# con-right-top.net
KiCad netlist of a schematic drawn in Altium Designer
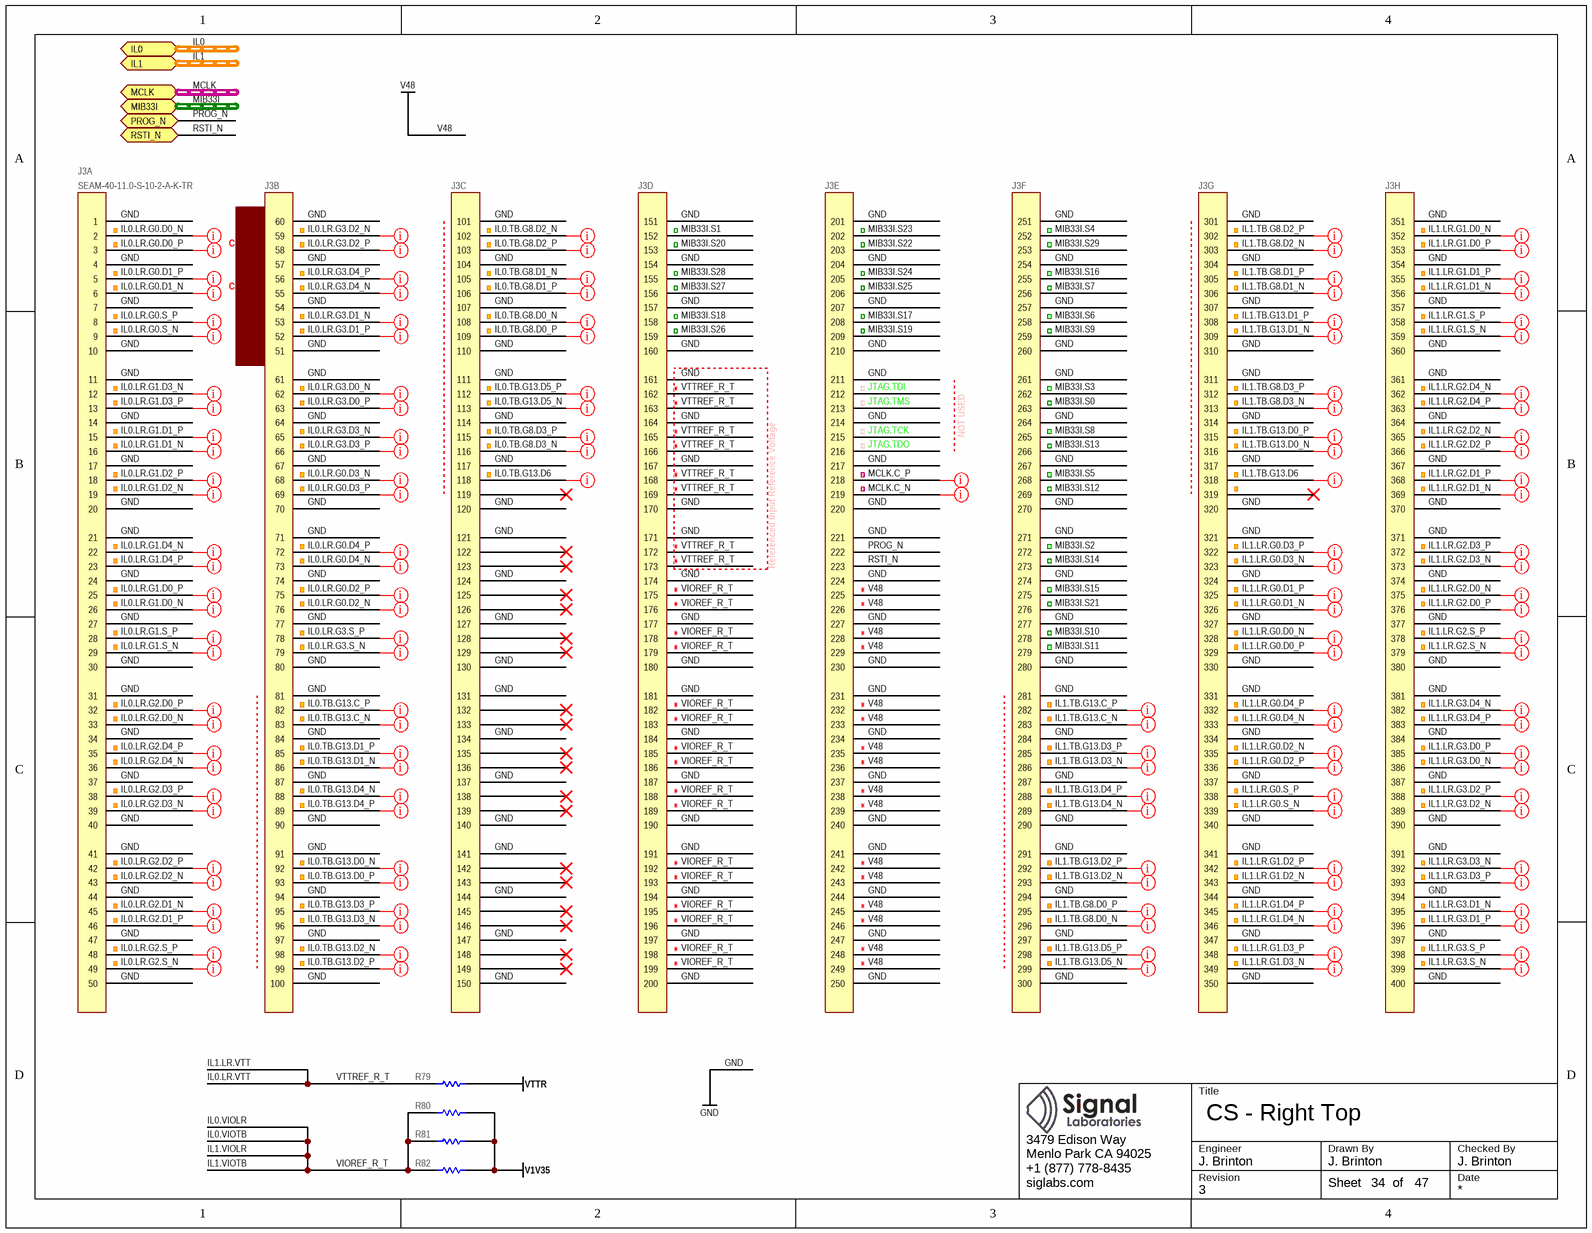
[diagram p0: con-right-top.SchDoc]

(export (version "E")
  (design (tool "Eeschema 10.0.6"))
  (components
    (comp (ref "J3")
      (value "SEAM-40-11.0-S-10-2-A-K-TR")
      (footprint "samtec:SEAM-40-11.0-S-10-2-A-K-TR")
      (description "Terminal Array Assembly, Surface Mount, 0.050\" Pitch, 400 Pins")
      (fields (field (name "MANUFACTURER") "Samtec"))
      (libsource (lib "samtec") (part "SEAM-40-11.0-S-10-2-A-K-TR"))
    )
    (comp (ref "R79")
      (value "SOLDER_LINK")
      (footprint "SOLDERLINK0603X26N")
      (description "Solder Link")
      (libsource (lib "generic") (part "RES"))
    )
    (comp (ref "R80")
      (value "SOLDER_LINK")
      (footprint "SOLDERLINK0603X26N")
      (description "Solder Link")
      (libsource (lib "generic") (part "RES"))
    )
    (comp (ref "R81")
      (value "SOLDER_LINK")
      (footprint "SOLDERLINK0603X26N")
      (description "Solder Link")
      (libsource (lib "generic") (part "RES"))
    )
    (comp (ref "R82")
      (value "SOLDER_LINK")
      (footprint "SOLDERLINK0603X26N")
      (description "Solder Link")
      (libsource (lib "generic") (part "RES"))
    )
  )
  (nets
    (net (code "5") (name "/IL0.LR.G0.D0_N") (class "Default")
      (node (ref "J3") (pin "2") (pinfunction "2_2") (pintype "passive"))
    )
    (net (code "6") (name "/IL0.LR.G0.D0_P") (class "Default")
      (node (ref "J3") (pin "3") (pinfunction "3_3") (pintype "passive"))
    )
    (net (code "7") (name "/IL0.LR.G0.D1_N") (class "Default")
      (node (ref "J3") (pin "6") (pinfunction "6_6") (pintype "passive"))
    )
    (net (code "8") (name "/IL0.LR.G0.D1_P") (class "Default")
      (node (ref "J3") (pin "5") (pinfunction "5_5") (pintype "passive"))
    )
    (net (code "9") (name "/IL0.LR.G0.D2_N") (class "Default")
      (node (ref "J3") (pin "76") (pinfunction "76_76") (pintype "passive"))
    )
    (net (code "10") (name "/IL0.LR.G0.D2_P") (class "Default")
      (node (ref "J3") (pin "75") (pinfunction "75_75") (pintype "passive"))
    )
    (net (code "11") (name "/IL0.LR.G0.D3_N") (class "Default")
      (node (ref "J3") (pin "68") (pinfunction "68_68") (pintype "passive"))
    )
    (net (code "12") (name "/IL0.LR.G0.D3_P") (class "Default")
      (node (ref "J3") (pin "69") (pinfunction "69_69") (pintype "passive"))
    )
    (net (code "13") (name "/IL0.LR.G0.D4_N") (class "Default")
      (node (ref "J3") (pin "73") (pinfunction "73_73") (pintype "passive"))
    )
    (net (code "14") (name "/IL0.LR.G0.D4_P") (class "Default")
      (node (ref "J3") (pin "72") (pinfunction "72_72") (pintype "passive"))
    )
    (net (code "15") (name "/IL0.LR.G0.S_N") (class "Default")
      (node (ref "J3") (pin "9") (pinfunction "9_9") (pintype "passive"))
    )
    (net (code "16") (name "/IL0.LR.G0.S_P") (class "Default")
      (node (ref "J3") (pin "8") (pinfunction "8_8") (pintype "passive"))
    )
    (net (code "17") (name "/IL0.LR.G1.D0_N") (class "Default")
      (node (ref "J3") (pin "26") (pinfunction "26_26") (pintype "passive"))
    )
    (net (code "18") (name "/IL0.LR.G1.D0_P") (class "Default")
      (node (ref "J3") (pin "25") (pinfunction "25_25") (pintype "passive"))
    )
    (net (code "19") (name "/IL0.LR.G1.D1_N") (class "Default")
      (node (ref "J3") (pin "16") (pinfunction "16_16") (pintype "passive"))
    )
    (net (code "20") (name "/IL0.LR.G1.D1_P") (class "Default")
      (node (ref "J3") (pin "15") (pinfunction "15_15") (pintype "passive"))
    )
    (net (code "21") (name "/IL0.LR.G1.D2_N") (class "Default")
      (node (ref "J3") (pin "19") (pinfunction "19_19") (pintype "passive"))
    )
    (net (code "22") (name "/IL0.LR.G1.D2_P") (class "Default")
      (node (ref "J3") (pin "18") (pinfunction "18_18") (pintype "passive"))
    )
    (net (code "23") (name "/IL0.LR.G1.D3_N") (class "Default")
      (node (ref "J3") (pin "12") (pinfunction "12_12") (pintype "passive"))
    )
    (net (code "24") (name "/IL0.LR.G1.D3_P") (class "Default")
      (node (ref "J3") (pin "13") (pinfunction "13_13") (pintype "passive"))
    )
    (net (code "25") (name "/IL0.LR.G1.D4_N") (class "Default")
      (node (ref "J3") (pin "22") (pinfunction "22_22") (pintype "passive"))
    )
    (net (code "26") (name "/IL0.LR.G1.D4_P") (class "Default")
      (node (ref "J3") (pin "23") (pinfunction "23_23") (pintype "passive"))
    )
    (net (code "27") (name "/IL0.LR.G1.S_N") (class "Default")
      (node (ref "J3") (pin "29") (pinfunction "29_29") (pintype "passive"))
    )
    (net (code "28") (name "/IL0.LR.G1.S_P") (class "Default")
      (node (ref "J3") (pin "28") (pinfunction "28_28") (pintype "passive"))
    )
    (net (code "29") (name "/IL0.LR.G2.D0_N") (class "Default")
      (node (ref "J3") (pin "33") (pinfunction "33_33") (pintype "passive"))
    )
    (net (code "30") (name "/IL0.LR.G2.D0_P") (class "Default")
      (node (ref "J3") (pin "32") (pinfunction "32_32") (pintype "passive"))
    )
    (net (code "31") (name "/IL0.LR.G2.D1_N") (class "Default")
      (node (ref "J3") (pin "45") (pinfunction "45_45") (pintype "passive"))
    )
    (net (code "32") (name "/IL0.LR.G2.D1_P") (class "Default")
      (node (ref "J3") (pin "46") (pinfunction "46_46") (pintype "passive"))
    )
    (net (code "33") (name "/IL0.LR.G2.D2_N") (class "Default")
      (node (ref "J3") (pin "43") (pinfunction "43_43") (pintype "passive"))
    )
    (net (code "34") (name "/IL0.LR.G2.D2_P") (class "Default")
      (node (ref "J3") (pin "42") (pinfunction "42_42") (pintype "passive"))
    )
    (net (code "35") (name "/IL0.LR.G2.D3_N") (class "Default")
      (node (ref "J3") (pin "39") (pinfunction "39_39") (pintype "passive"))
    )
    (net (code "36") (name "/IL0.LR.G2.D3_P") (class "Default")
      (node (ref "J3") (pin "38") (pinfunction "38_38") (pintype "passive"))
    )
    (net (code "37") (name "/IL0.LR.G2.D4_N") (class "Default")
      (node (ref "J3") (pin "36") (pinfunction "36_36") (pintype "passive"))
    )
    (net (code "38") (name "/IL0.LR.G2.D4_P") (class "Default")
      (node (ref "J3") (pin "35") (pinfunction "35_35") (pintype "passive"))
    )
    (net (code "39") (name "/IL0.LR.G2.S_N") (class "Default")
      (node (ref "J3") (pin "49") (pinfunction "49_49") (pintype "passive"))
    )
    (net (code "40") (name "/IL0.LR.G2.S_P") (class "Default")
      (node (ref "J3") (pin "48") (pinfunction "48_48") (pintype "passive"))
    )
    (net (code "41") (name "/IL0.LR.G3.D0_N") (class "Default")
      (node (ref "J3") (pin "62") (pinfunction "62_62") (pintype "passive"))
    )
    (net (code "42") (name "/IL0.LR.G3.D0_P") (class "Default")
      (node (ref "J3") (pin "63") (pinfunction "63_63") (pintype "passive"))
    )
    (net (code "43") (name "/IL0.LR.G3.D1_N") (class "Default")
      (node (ref "J3") (pin "53") (pinfunction "53_53") (pintype "passive"))
    )
    (net (code "44") (name "/IL0.LR.G3.D1_P") (class "Default")
      (node (ref "J3") (pin "52") (pinfunction "52_52") (pintype "passive"))
    )
    (net (code "45") (name "/IL0.LR.G3.D2_N") (class "Default")
      (node (ref "J3") (pin "59") (pinfunction "59_59") (pintype "passive"))
    )
    (net (code "46") (name "/IL0.LR.G3.D2_P") (class "Default")
      (node (ref "J3") (pin "58") (pinfunction "58_58") (pintype "passive"))
    )
    (net (code "47") (name "/IL0.LR.G3.D3_N") (class "Default")
      (node (ref "J3") (pin "65") (pinfunction "65_65") (pintype "passive"))
    )
    (net (code "48") (name "/IL0.LR.G3.D3_P") (class "Default")
      (node (ref "J3") (pin "66") (pinfunction "66_66") (pintype "passive"))
    )
    (net (code "49") (name "/IL0.LR.G3.D4_N") (class "Default")
      (node (ref "J3") (pin "55") (pinfunction "55_55") (pintype "passive"))
    )
    (net (code "50") (name "/IL0.LR.G3.D4_P") (class "Default")
      (node (ref "J3") (pin "56") (pinfunction "56_56") (pintype "passive"))
    )
    (net (code "51") (name "/IL0.LR.G3.S_N") (class "Default")
      (node (ref "J3") (pin "79") (pinfunction "79_79") (pintype "passive"))
    )
    (net (code "52") (name "/IL0.LR.G3.S_P") (class "Default")
      (node (ref "J3") (pin "78") (pinfunction "78_78") (pintype "passive"))
    )
    (net (code "53") (name "/IL0.LR.VTT") (class "Default")
      (node (ref "J3") (pin "162") (pinfunction "162_162") (pintype "passive"))
      (node (ref "J3") (pin "163") (pinfunction "163_163") (pintype "passive"))
      (node (ref "J3") (pin "165") (pinfunction "165_165") (pintype "passive"))
      (node (ref "J3") (pin "166") (pinfunction "166_166") (pintype "passive"))
      (node (ref "J3") (pin "168") (pinfunction "168_168") (pintype "passive"))
      (node (ref "J3") (pin "169") (pinfunction "169_169") (pintype "passive"))
      (node (ref "J3") (pin "172") (pinfunction "172_172") (pintype "passive"))
      (node (ref "J3") (pin "173") (pinfunction "173_173") (pintype "passive"))
      (node (ref "R79") (pin "2") (pinfunction "2_2") (pintype "passive"))
    )
    (net (code "54") (name "/IL0.TB.G8.D0_N") (class "Default")
      (node (ref "J3") (pin "108") (pinfunction "108_108") (pintype "passive"))
    )
    (net (code "55") (name "/IL0.TB.G8.D0_P") (class "Default")
      (node (ref "J3") (pin "109") (pinfunction "109_109") (pintype "passive"))
    )
    (net (code "56") (name "/IL0.TB.G8.D1_N") (class "Default")
      (node (ref "J3") (pin "105") (pinfunction "105_105") (pintype "passive"))
    )
    (net (code "57") (name "/IL0.TB.G8.D1_P") (class "Default")
      (node (ref "J3") (pin "106") (pinfunction "106_106") (pintype "passive"))
    )
    (net (code "58") (name "/IL0.TB.G8.D2_N") (class "Default")
      (node (ref "J3") (pin "102") (pinfunction "102_102") (pintype "passive"))
    )
    (net (code "59") (name "/IL0.TB.G8.D2_P") (class "Default")
      (node (ref "J3") (pin "103") (pinfunction "103_103") (pintype "passive"))
    )
    (net (code "60") (name "/IL0.TB.G8.D3_N") (class "Default")
      (node (ref "J3") (pin "116") (pinfunction "116_116") (pintype "passive"))
    )
    (net (code "61") (name "/IL0.TB.G8.D3_P") (class "Default")
      (node (ref "J3") (pin "115") (pinfunction "115_115") (pintype "passive"))
    )
    (net (code "62") (name "/IL0.TB.G13.C_N") (class "Default")
      (node (ref "J3") (pin "83") (pinfunction "83_83") (pintype "passive"))
    )
    (net (code "63") (name "/IL0.TB.G13.C_P") (class "Default")
      (node (ref "J3") (pin "82") (pinfunction "82_82") (pintype "passive"))
    )
    (net (code "64") (name "/IL0.TB.G13.D0_N") (class "Default")
      (node (ref "J3") (pin "92") (pinfunction "92_92") (pintype "passive"))
    )
    (net (code "65") (name "/IL0.TB.G13.D0_P") (class "Default")
      (node (ref "J3") (pin "93") (pinfunction "93_93") (pintype "passive"))
    )
    (net (code "66") (name "/IL0.TB.G13.D1_N") (class "Default")
      (node (ref "J3") (pin "86") (pinfunction "86_86") (pintype "passive"))
    )
    (net (code "67") (name "/IL0.TB.G13.D1_P") (class "Default")
      (node (ref "J3") (pin "85") (pinfunction "85_85") (pintype "passive"))
    )
    (net (code "68") (name "/IL0.TB.G13.D2_N") (class "Default")
      (node (ref "J3") (pin "98") (pinfunction "98_98") (pintype "passive"))
    )
    (net (code "69") (name "/IL0.TB.G13.D2_P") (class "Default")
      (node (ref "J3") (pin "99") (pinfunction "99_99") (pintype "passive"))
    )
    (net (code "70") (name "/IL0.TB.G13.D3_N") (class "Default")
      (node (ref "J3") (pin "96") (pinfunction "96_96") (pintype "passive"))
    )
    (net (code "71") (name "/IL0.TB.G13.D3_P") (class "Default")
      (node (ref "J3") (pin "95") (pinfunction "95_95") (pintype "passive"))
    )
    (net (code "72") (name "/IL0.TB.G13.D4_N") (class "Default")
      (node (ref "J3") (pin "88") (pinfunction "88_88") (pintype "passive"))
    )
    (net (code "73") (name "/IL0.TB.G13.D4_P") (class "Default")
      (node (ref "J3") (pin "89") (pinfunction "89_89") (pintype "passive"))
    )
    (net (code "74") (name "/IL0.TB.G13.D5_N") (class "Default")
      (node (ref "J3") (pin "113") (pinfunction "113_113") (pintype "passive"))
    )
    (net (code "75") (name "/IL0.TB.G13.D5_P") (class "Default")
      (node (ref "J3") (pin "112") (pinfunction "112_112") (pintype "passive"))
    )
    (net (code "76") (name "/IL0.TB.G13.D6") (class "Default")
      (node (ref "J3") (pin "118") (pinfunction "118_118") (pintype "passive"))
    )
    (net (code "77") (name "/IL0.VIOLR") (class "Default")
      (node (ref "J3") (pin "175") (pinfunction "175_175") (pintype "passive"))
      (node (ref "J3") (pin "176") (pinfunction "176_176") (pintype "passive"))
      (node (ref "J3") (pin "178") (pinfunction "178_178") (pintype "passive"))
      (node (ref "J3") (pin "179") (pinfunction "179_179") (pintype "passive"))
      (node (ref "J3") (pin "182") (pinfunction "182_182") (pintype "passive"))
      (node (ref "J3") (pin "183") (pinfunction "183_183") (pintype "passive"))
      (node (ref "J3") (pin "185") (pinfunction "185_185") (pintype "passive"))
      (node (ref "J3") (pin "186") (pinfunction "186_186") (pintype "passive"))
      (node (ref "J3") (pin "188") (pinfunction "188_188") (pintype "passive"))
      (node (ref "J3") (pin "189") (pinfunction "189_189") (pintype "passive"))
      (node (ref "J3") (pin "192") (pinfunction "192_192") (pintype "passive"))
      (node (ref "J3") (pin "193") (pinfunction "193_193") (pintype "passive"))
      (node (ref "J3") (pin "195") (pinfunction "195_195") (pintype "passive"))
      (node (ref "J3") (pin "196") (pinfunction "196_196") (pintype "passive"))
      (node (ref "J3") (pin "198") (pinfunction "198_198") (pintype "passive"))
      (node (ref "J3") (pin "199") (pinfunction "199_199") (pintype "passive"))
      (node (ref "R80") (pin "2") (pinfunction "2_2") (pintype "passive"))
      (node (ref "R81") (pin "2") (pinfunction "2_2") (pintype "passive"))
      (node (ref "R82") (pin "2") (pinfunction "2_2") (pintype "passive"))
    )
    (net (code "78") (name "/IL1.LR.G0.D0_N") (class "Default")
      (node (ref "J3") (pin "328") (pinfunction "328_328") (pintype "passive"))
    )
    (net (code "79") (name "/IL1.LR.G0.D0_P") (class "Default")
      (node (ref "J3") (pin "329") (pinfunction "329_329") (pintype "passive"))
    )
    (net (code "80") (name "/IL1.LR.G0.D1_N") (class "Default")
      (node (ref "J3") (pin "326") (pinfunction "326_326") (pintype "passive"))
    )
    (net (code "81") (name "/IL1.LR.G0.D1_P") (class "Default")
      (node (ref "J3") (pin "325") (pinfunction "325_325") (pintype "passive"))
    )
    (net (code "82") (name "/IL1.LR.G0.D2_N") (class "Default")
      (node (ref "J3") (pin "335") (pinfunction "335_335") (pintype "passive"))
    )
    (net (code "83") (name "/IL1.LR.G0.D2_P") (class "Default")
      (node (ref "J3") (pin "336") (pinfunction "336_336") (pintype "passive"))
    )
    (net (code "84") (name "/IL1.LR.G0.D3_N") (class "Default")
      (node (ref "J3") (pin "323") (pinfunction "323_323") (pintype "passive"))
    )
    (net (code "85") (name "/IL1.LR.G0.D3_P") (class "Default")
      (node (ref "J3") (pin "322") (pinfunction "322_322") (pintype "passive"))
    )
    (net (code "86") (name "/IL1.LR.G0.D4_N") (class "Default")
      (node (ref "J3") (pin "333") (pinfunction "333_333") (pintype "passive"))
    )
    (net (code "87") (name "/IL1.LR.G0.D4_P") (class "Default")
      (node (ref "J3") (pin "332") (pinfunction "332_332") (pintype "passive"))
    )
    (net (code "88") (name "/IL1.LR.G0.S_N") (class "Default")
      (node (ref "J3") (pin "339") (pinfunction "339_339") (pintype "passive"))
    )
    (net (code "89") (name "/IL1.LR.G0.S_P") (class "Default")
      (node (ref "J3") (pin "338") (pinfunction "338_338") (pintype "passive"))
    )
    (net (code "90") (name "/IL1.LR.G1.D0_N") (class "Default")
      (node (ref "J3") (pin "352") (pinfunction "352_352") (pintype "passive"))
    )
    (net (code "91") (name "/IL1.LR.G1.D0_P") (class "Default")
      (node (ref "J3") (pin "353") (pinfunction "353_353") (pintype "passive"))
    )
    (net (code "92") (name "/IL1.LR.G1.D1_N") (class "Default")
      (node (ref "J3") (pin "356") (pinfunction "356_356") (pintype "passive"))
    )
    (net (code "93") (name "/IL1.LR.G1.D1_P") (class "Default")
      (node (ref "J3") (pin "355") (pinfunction "355_355") (pintype "passive"))
    )
    (net (code "94") (name "/IL1.LR.G1.D2_N") (class "Default")
      (node (ref "J3") (pin "343") (pinfunction "343_343") (pintype "passive"))
    )
    (net (code "95") (name "/IL1.LR.G1.D2_P") (class "Default")
      (node (ref "J3") (pin "342") (pinfunction "342_342") (pintype "passive"))
    )
    (net (code "96") (name "/IL1.LR.G1.D3_N") (class "Default")
      (node (ref "J3") (pin "349") (pinfunction "349_349") (pintype "passive"))
    )
    (net (code "97") (name "/IL1.LR.G1.D3_P") (class "Default")
      (node (ref "J3") (pin "348") (pinfunction "348_348") (pintype "passive"))
    )
    (net (code "98") (name "/IL1.LR.G1.D4_N") (class "Default")
      (node (ref "J3") (pin "346") (pinfunction "346_346") (pintype "passive"))
    )
    (net (code "99") (name "/IL1.LR.G1.D4_P") (class "Default")
      (node (ref "J3") (pin "345") (pinfunction "345_345") (pintype "passive"))
    )
    (net (code "100") (name "/IL1.LR.G1.S_N") (class "Default")
      (node (ref "J3") (pin "359") (pinfunction "359_359") (pintype "passive"))
    )
    (net (code "101") (name "/IL1.LR.G1.S_P") (class "Default")
      (node (ref "J3") (pin "358") (pinfunction "358_358") (pintype "passive"))
    )
    (net (code "102") (name "/IL1.LR.G2.D0_N") (class "Default")
      (node (ref "J3") (pin "375") (pinfunction "375_375") (pintype "passive"))
    )
    (net (code "103") (name "/IL1.LR.G2.D0_P") (class "Default")
      (node (ref "J3") (pin "376") (pinfunction "376_376") (pintype "passive"))
    )
    (net (code "104") (name "/IL1.LR.G2.D1_N") (class "Default")
      (node (ref "J3") (pin "369") (pinfunction "369_369") (pintype "passive"))
    )
    (net (code "105") (name "/IL1.LR.G2.D1_P") (class "Default")
      (node (ref "J3") (pin "368") (pinfunction "368_368") (pintype "passive"))
    )
    (net (code "106") (name "/IL1.LR.G2.D2_N") (class "Default")
      (node (ref "J3") (pin "365") (pinfunction "365_365") (pintype "passive"))
    )
    (net (code "107") (name "/IL1.LR.G2.D2_P") (class "Default")
      (node (ref "J3") (pin "366") (pinfunction "366_366") (pintype "passive"))
    )
    (net (code "108") (name "/IL1.LR.G2.D3_N") (class "Default")
      (node (ref "J3") (pin "373") (pinfunction "373_373") (pintype "passive"))
    )
    (net (code "109") (name "/IL1.LR.G2.D3_P") (class "Default")
      (node (ref "J3") (pin "372") (pinfunction "372_372") (pintype "passive"))
    )
    (net (code "110") (name "/IL1.LR.G2.D4_N") (class "Default")
      (node (ref "J3") (pin "362") (pinfunction "362_362") (pintype "passive"))
    )
    (net (code "111") (name "/IL1.LR.G2.D4_P") (class "Default")
      (node (ref "J3") (pin "363") (pinfunction "363_363") (pintype "passive"))
    )
    (net (code "112") (name "/IL1.LR.G2.S_N") (class "Default")
      (node (ref "J3") (pin "379") (pinfunction "379_379") (pintype "passive"))
    )
    (net (code "113") (name "/IL1.LR.G2.S_P") (class "Default")
      (node (ref "J3") (pin "378") (pinfunction "378_378") (pintype "passive"))
    )
    (net (code "114") (name "/IL1.LR.G3.D0_N") (class "Default")
      (node (ref "J3") (pin "386") (pinfunction "386_386") (pintype "passive"))
    )
    (net (code "115") (name "/IL1.LR.G3.D0_P") (class "Default")
      (node (ref "J3") (pin "385") (pinfunction "385_385") (pintype "passive"))
    )
    (net (code "116") (name "/IL1.LR.G3.D1_N") (class "Default")
      (node (ref "J3") (pin "395") (pinfunction "395_395") (pintype "passive"))
    )
    (net (code "117") (name "/IL1.LR.G3.D1_P") (class "Default")
      (node (ref "J3") (pin "396") (pinfunction "396_396") (pintype "passive"))
    )
    (net (code "118") (name "/IL1.LR.G3.D2_N") (class "Default")
      (node (ref "J3") (pin "389") (pinfunction "389_389") (pintype "passive"))
    )
    (net (code "119") (name "/IL1.LR.G3.D2_P") (class "Default")
      (node (ref "J3") (pin "388") (pinfunction "388_388") (pintype "passive"))
    )
    (net (code "120") (name "/IL1.LR.G3.D3_N") (class "Default")
      (node (ref "J3") (pin "392") (pinfunction "392_392") (pintype "passive"))
    )
    (net (code "121") (name "/IL1.LR.G3.D3_P") (class "Default")
      (node (ref "J3") (pin "393") (pinfunction "393_393") (pintype "passive"))
    )
    (net (code "122") (name "/IL1.LR.G3.D4_N") (class "Default")
      (node (ref "J3") (pin "382") (pinfunction "382_382") (pintype "passive"))
    )
    (net (code "123") (name "/IL1.LR.G3.D4_P") (class "Default")
      (node (ref "J3") (pin "383") (pinfunction "383_383") (pintype "passive"))
    )
    (net (code "124") (name "/IL1.LR.G3.S_N") (class "Default")
      (node (ref "J3") (pin "399") (pinfunction "399_399") (pintype "passive"))
    )
    (net (code "125") (name "/IL1.LR.G3.S_P") (class "Default")
      (node (ref "J3") (pin "398") (pinfunction "398_398") (pintype "passive"))
    )
    (net (code "126") (name "/IL1.TB.G8.D0_N") (class "Default")
      (node (ref "J3") (pin "296") (pinfunction "296_296") (pintype "passive"))
    )
    (net (code "127") (name "/IL1.TB.G8.D0_P") (class "Default")
      (node (ref "J3") (pin "295") (pinfunction "295_295") (pintype "passive"))
    )
    (net (code "128") (name "/IL1.TB.G8.D1_N") (class "Default")
      (node (ref "J3") (pin "306") (pinfunction "306_306") (pintype "passive"))
    )
    (net (code "129") (name "/IL1.TB.G8.D1_P") (class "Default")
      (node (ref "J3") (pin "305") (pinfunction "305_305") (pintype "passive"))
    )
    (net (code "130") (name "/IL1.TB.G8.D2_N") (class "Default")
      (node (ref "J3") (pin "303") (pinfunction "303_303") (pintype "passive"))
    )
    (net (code "131") (name "/IL1.TB.G8.D2_P") (class "Default")
      (node (ref "J3") (pin "302") (pinfunction "302_302") (pintype "passive"))
    )
    (net (code "132") (name "/IL1.TB.G8.D3_N") (class "Default")
      (node (ref "J3") (pin "313") (pinfunction "313_313") (pintype "passive"))
    )
    (net (code "133") (name "/IL1.TB.G8.D3_P") (class "Default")
      (node (ref "J3") (pin "312") (pinfunction "312_312") (pintype "passive"))
    )
    (net (code "134") (name "/IL1.TB.G13.C_N") (class "Default")
      (node (ref "J3") (pin "283") (pinfunction "283_283") (pintype "passive"))
    )
    (net (code "135") (name "/IL1.TB.G13.C_P") (class "Default")
      (node (ref "J3") (pin "282") (pinfunction "282_282") (pintype "passive"))
    )
    (net (code "136") (name "/IL1.TB.G13.D0_N") (class "Default")
      (node (ref "J3") (pin "316") (pinfunction "316_316") (pintype "passive"))
    )
    (net (code "137") (name "/IL1.TB.G13.D0_P") (class "Default")
      (node (ref "J3") (pin "315") (pinfunction "315_315") (pintype "passive"))
    )
    (net (code "138") (name "/IL1.TB.G13.D1_N") (class "Default")
      (node (ref "J3") (pin "309") (pinfunction "309_309") (pintype "passive"))
    )
    (net (code "139") (name "/IL1.TB.G13.D1_P") (class "Default")
      (node (ref "J3") (pin "308") (pinfunction "308_308") (pintype "passive"))
    )
    (net (code "140") (name "/IL1.TB.G13.D2_N") (class "Default")
      (node (ref "J3") (pin "293") (pinfunction "293_293") (pintype "passive"))
    )
    (net (code "141") (name "/IL1.TB.G13.D2_P") (class "Default")
      (node (ref "J3") (pin "292") (pinfunction "292_292") (pintype "passive"))
    )
    (net (code "142") (name "/IL1.TB.G13.D3_N") (class "Default")
      (node (ref "J3") (pin "286") (pinfunction "286_286") (pintype "passive"))
    )
    (net (code "143") (name "/IL1.TB.G13.D3_P") (class "Default")
      (node (ref "J3") (pin "285") (pinfunction "285_285") (pintype "passive"))
    )
    (net (code "144") (name "/IL1.TB.G13.D4_N") (class "Default")
      (node (ref "J3") (pin "289") (pinfunction "289_289") (pintype "passive"))
    )
    (net (code "145") (name "/IL1.TB.G13.D4_P") (class "Default")
      (node (ref "J3") (pin "288") (pinfunction "288_288") (pintype "passive"))
    )
    (net (code "146") (name "/IL1.TB.G13.D5_N") (class "Default")
      (node (ref "J3") (pin "299") (pinfunction "299_299") (pintype "passive"))
    )
    (net (code "147") (name "/IL1.TB.G13.D5_P") (class "Default")
      (node (ref "J3") (pin "298") (pinfunction "298_298") (pintype "passive"))
    )
    (net (code "148") (name "/IL1.TB.G13.D6") (class "Default")
      (node (ref "J3") (pin "318") (pinfunction "318_318") (pintype "passive"))
    )
    (net (code "149") (name "/MCLK.C_N") (class "Default")
      (node (ref "J3") (pin "219") (pinfunction "219_219") (pintype "passive"))
    )
    (net (code "150") (name "/MCLK.C_P") (class "Default")
      (node (ref "J3") (pin "218") (pinfunction "218_218") (pintype "passive"))
    )
    (net (code "151") (name "/MIB33I.S0") (class "Default")
      (node (ref "J3") (pin "263") (pinfunction "263_263") (pintype "passive"))
    )
    (net (code "152") (name "/MIB33I.S1") (class "Default")
      (node (ref "J3") (pin "152") (pinfunction "152_152") (pintype "passive"))
    )
    (net (code "153") (name "/MIB33I.S2") (class "Default")
      (node (ref "J3") (pin "272") (pinfunction "272_272") (pintype "passive"))
    )
    (net (code "154") (name "/MIB33I.S3") (class "Default")
      (node (ref "J3") (pin "262") (pinfunction "262_262") (pintype "passive"))
    )
    (net (code "155") (name "/MIB33I.S4") (class "Default")
      (node (ref "J3") (pin "252") (pinfunction "252_252") (pintype "passive"))
    )
    (net (code "156") (name "/MIB33I.S5") (class "Default")
      (node (ref "J3") (pin "268") (pinfunction "268_268") (pintype "passive"))
    )
    (net (code "157") (name "/MIB33I.S6") (class "Default")
      (node (ref "J3") (pin "258") (pinfunction "258_258") (pintype "passive"))
    )
    (net (code "158") (name "/MIB33I.S7") (class "Default")
      (node (ref "J3") (pin "256") (pinfunction "256_256") (pintype "passive"))
    )
    (net (code "159") (name "/MIB33I.S8") (class "Default")
      (node (ref "J3") (pin "265") (pinfunction "265_265") (pintype "passive"))
    )
    (net (code "160") (name "/MIB33I.S9") (class "Default")
      (node (ref "J3") (pin "259") (pinfunction "259_259") (pintype "passive"))
    )
    (net (code "161") (name "/MIB33I.S10") (class "Default")
      (node (ref "J3") (pin "278") (pinfunction "278_278") (pintype "passive"))
    )
    (net (code "162") (name "/MIB33I.S11") (class "Default")
      (node (ref "J3") (pin "279") (pinfunction "279_279") (pintype "passive"))
    )
    (net (code "163") (name "/MIB33I.S12") (class "Default")
      (node (ref "J3") (pin "269") (pinfunction "269_269") (pintype "passive"))
    )
    (net (code "164") (name "/MIB33I.S13") (class "Default")
      (node (ref "J3") (pin "266") (pinfunction "266_266") (pintype "passive"))
    )
    (net (code "165") (name "/MIB33I.S14") (class "Default")
      (node (ref "J3") (pin "273") (pinfunction "273_273") (pintype "passive"))
    )
    (net (code "166") (name "/MIB33I.S15") (class "Default")
      (node (ref "J3") (pin "275") (pinfunction "275_275") (pintype "passive"))
    )
    (net (code "167") (name "/MIB33I.S16") (class "Default")
      (node (ref "J3") (pin "255") (pinfunction "255_255") (pintype "passive"))
    )
    (net (code "168") (name "/MIB33I.S17") (class "Default")
      (node (ref "J3") (pin "208") (pinfunction "208_208") (pintype "passive"))
    )
    (net (code "169") (name "/MIB33I.S18") (class "Default")
      (node (ref "J3") (pin "158") (pinfunction "158_158") (pintype "passive"))
    )
    (net (code "170") (name "/MIB33I.S19") (class "Default")
      (node (ref "J3") (pin "209") (pinfunction "209_209") (pintype "passive"))
    )
    (net (code "171") (name "/MIB33I.S20") (class "Default")
      (node (ref "J3") (pin "153") (pinfunction "153_153") (pintype "passive"))
    )
    (net (code "172") (name "/MIB33I.S21") (class "Default")
      (node (ref "J3") (pin "276") (pinfunction "276_276") (pintype "passive"))
    )
    (net (code "173") (name "/MIB33I.S22") (class "Default")
      (node (ref "J3") (pin "203") (pinfunction "203_203") (pintype "passive"))
    )
    (net (code "174") (name "/MIB33I.S23") (class "Default")
      (node (ref "J3") (pin "202") (pinfunction "202_202") (pintype "passive"))
    )
    (net (code "175") (name "/MIB33I.S24") (class "Default")
      (node (ref "J3") (pin "205") (pinfunction "205_205") (pintype "passive"))
    )
    (net (code "176") (name "/MIB33I.S25") (class "Default")
      (node (ref "J3") (pin "206") (pinfunction "206_206") (pintype "passive"))
    )
    (net (code "177") (name "/MIB33I.S26") (class "Default")
      (node (ref "J3") (pin "159") (pinfunction "159_159") (pintype "passive"))
    )
    (net (code "178") (name "/MIB33I.S27") (class "Default")
      (node (ref "J3") (pin "156") (pinfunction "156_156") (pintype "passive"))
    )
    (net (code "179") (name "/MIB33I.S28") (class "Default")
      (node (ref "J3") (pin "155") (pinfunction "155_155") (pintype "passive"))
    )
    (net (code "180") (name "/MIB33I.S29") (class "Default")
      (node (ref "J3") (pin "253") (pinfunction "253_253") (pintype "passive"))
    )
    (net (code "181") (name "/PROG_N") (class "Default")
      (node (ref "J3") (pin "222") (pinfunction "222_222") (pintype "passive"))
    )
    (net (code "182") (name "/RSTI_N") (class "Default")
      (node (ref "J3") (pin "223") (pinfunction "223_223") (pintype "passive"))
    )
    (net (code "187") (name "GND") (class "Default")
      (node (ref "J3") (pin "1") (pinfunction "1_1") (pintype "passive"))
      (node (ref "J3") (pin "10") (pinfunction "10_10") (pintype "passive"))
      (node (ref "J3") (pin "100") (pinfunction "100_100") (pintype "passive"))
      (node (ref "J3") (pin "101") (pinfunction "101_101") (pintype "passive"))
      (node (ref "J3") (pin "104") (pinfunction "104_104") (pintype "passive"))
      (node (ref "J3") (pin "107") (pinfunction "107_107") (pintype "passive"))
      (node (ref "J3") (pin "11") (pinfunction "11_11") (pintype "passive"))
      (node (ref "J3") (pin "110") (pinfunction "110_110") (pintype "passive"))
      (node (ref "J3") (pin "111") (pinfunction "111_111") (pintype "passive"))
      (node (ref "J3") (pin "114") (pinfunction "114_114") (pintype "passive"))
      (node (ref "J3") (pin "117") (pinfunction "117_117") (pintype "passive"))
      (node (ref "J3") (pin "120") (pinfunction "120_120") (pintype "passive"))
      (node (ref "J3") (pin "121") (pinfunction "121_121") (pintype "passive"))
      (node (ref "J3") (pin "124") (pinfunction "124_124") (pintype "passive"))
      (node (ref "J3") (pin "127") (pinfunction "127_127") (pintype "passive"))
      (node (ref "J3") (pin "130") (pinfunction "130_130") (pintype "passive"))
      (node (ref "J3") (pin "131") (pinfunction "131_131") (pintype "passive"))
      (node (ref "J3") (pin "134") (pinfunction "134_134") (pintype "passive"))
      (node (ref "J3") (pin "137") (pinfunction "137_137") (pintype "passive"))
      (node (ref "J3") (pin "14") (pinfunction "14_14") (pintype "passive"))
      (node (ref "J3") (pin "140") (pinfunction "140_140") (pintype "passive"))
      (node (ref "J3") (pin "141") (pinfunction "141_141") (pintype "passive"))
      (node (ref "J3") (pin "144") (pinfunction "144_144") (pintype "passive"))
      (node (ref "J3") (pin "147") (pinfunction "147_147") (pintype "passive"))
      (node (ref "J3") (pin "150") (pinfunction "150_150") (pintype "passive"))
      (node (ref "J3") (pin "151") (pinfunction "151_151") (pintype "passive"))
      (node (ref "J3") (pin "154") (pinfunction "154_154") (pintype "passive"))
      (node (ref "J3") (pin "157") (pinfunction "157_157") (pintype "passive"))
      (node (ref "J3") (pin "160") (pinfunction "160_160") (pintype "passive"))
      (node (ref "J3") (pin "161") (pinfunction "161_161") (pintype "passive"))
      (node (ref "J3") (pin "164") (pinfunction "164_164") (pintype "passive"))
      (node (ref "J3") (pin "167") (pinfunction "167_167") (pintype "passive"))
      (node (ref "J3") (pin "17") (pinfunction "17_17") (pintype "passive"))
      (node (ref "J3") (pin "170") (pinfunction "170_170") (pintype "passive"))
      (node (ref "J3") (pin "171") (pinfunction "171_171") (pintype "passive"))
      (node (ref "J3") (pin "174") (pinfunction "174_174") (pintype "passive"))
      (node (ref "J3") (pin "177") (pinfunction "177_177") (pintype "passive"))
      (node (ref "J3") (pin "180") (pinfunction "180_180") (pintype "passive"))
      (node (ref "J3") (pin "181") (pinfunction "181_181") (pintype "passive"))
      (node (ref "J3") (pin "184") (pinfunction "184_184") (pintype "passive"))
      (node (ref "J3") (pin "187") (pinfunction "187_187") (pintype "passive"))
      (node (ref "J3") (pin "190") (pinfunction "190_190") (pintype "passive"))
      (node (ref "J3") (pin "191") (pinfunction "191_191") (pintype "passive"))
      (node (ref "J3") (pin "194") (pinfunction "194_194") (pintype "passive"))
      (node (ref "J3") (pin "197") (pinfunction "197_197") (pintype "passive"))
      (node (ref "J3") (pin "20") (pinfunction "20_20") (pintype "passive"))
      (node (ref "J3") (pin "200") (pinfunction "200_200") (pintype "passive"))
      (node (ref "J3") (pin "201") (pinfunction "201_201") (pintype "passive"))
      (node (ref "J3") (pin "204") (pinfunction "204_204") (pintype "passive"))
      (node (ref "J3") (pin "207") (pinfunction "207_207") (pintype "passive"))
      (node (ref "J3") (pin "21") (pinfunction "21_21") (pintype "passive"))
      (node (ref "J3") (pin "210") (pinfunction "210_210") (pintype "passive"))
      (node (ref "J3") (pin "211") (pinfunction "211_211") (pintype "passive"))
      (node (ref "J3") (pin "214") (pinfunction "214_214") (pintype "passive"))
      (node (ref "J3") (pin "217") (pinfunction "217_217") (pintype "passive"))
      (node (ref "J3") (pin "220") (pinfunction "220_220") (pintype "passive"))
      (node (ref "J3") (pin "221") (pinfunction "221_221") (pintype "passive"))
      (node (ref "J3") (pin "224") (pinfunction "224_224") (pintype "passive"))
      (node (ref "J3") (pin "227") (pinfunction "227_227") (pintype "passive"))
      (node (ref "J3") (pin "230") (pinfunction "230_230") (pintype "passive"))
      (node (ref "J3") (pin "231") (pinfunction "231_231") (pintype "passive"))
      (node (ref "J3") (pin "234") (pinfunction "234_234") (pintype "passive"))
      (node (ref "J3") (pin "237") (pinfunction "237_237") (pintype "passive"))
      (node (ref "J3") (pin "24") (pinfunction "24_24") (pintype "passive"))
      (node (ref "J3") (pin "240") (pinfunction "240_240") (pintype "passive"))
      (node (ref "J3") (pin "241") (pinfunction "241_241") (pintype "passive"))
      (node (ref "J3") (pin "244") (pinfunction "244_244") (pintype "passive"))
      (node (ref "J3") (pin "247") (pinfunction "247_247") (pintype "passive"))
      (node (ref "J3") (pin "250") (pinfunction "250_250") (pintype "passive"))
      (node (ref "J3") (pin "251") (pinfunction "251_251") (pintype "passive"))
      (node (ref "J3") (pin "254") (pinfunction "254_254") (pintype "passive"))
      (node (ref "J3") (pin "257") (pinfunction "257_257") (pintype "passive"))
      (node (ref "J3") (pin "260") (pinfunction "260_260") (pintype "passive"))
      (node (ref "J3") (pin "261") (pinfunction "261_261") (pintype "passive"))
      (node (ref "J3") (pin "264") (pinfunction "264_264") (pintype "passive"))
      (node (ref "J3") (pin "267") (pinfunction "267_267") (pintype "passive"))
      (node (ref "J3") (pin "27") (pinfunction "27_27") (pintype "passive"))
      (node (ref "J3") (pin "270") (pinfunction "270_270") (pintype "passive"))
      (node (ref "J3") (pin "271") (pinfunction "271_271") (pintype "passive"))
      (node (ref "J3") (pin "274") (pinfunction "274_274") (pintype "passive"))
      (node (ref "J3") (pin "277") (pinfunction "277_277") (pintype "passive"))
      (node (ref "J3") (pin "280") (pinfunction "280_280") (pintype "passive"))
      (node (ref "J3") (pin "281") (pinfunction "281_281") (pintype "passive"))
      (node (ref "J3") (pin "284") (pinfunction "284_284") (pintype "passive"))
      (node (ref "J3") (pin "287") (pinfunction "287_287") (pintype "passive"))
      (node (ref "J3") (pin "290") (pinfunction "290_290") (pintype "passive"))
      (node (ref "J3") (pin "291") (pinfunction "291_291") (pintype "passive"))
      (node (ref "J3") (pin "294") (pinfunction "294_294") (pintype "passive"))
      (node (ref "J3") (pin "297") (pinfunction "297_297") (pintype "passive"))
      (node (ref "J3") (pin "30") (pinfunction "30_30") (pintype "passive"))
      (node (ref "J3") (pin "300") (pinfunction "300_300") (pintype "passive"))
      (node (ref "J3") (pin "301") (pinfunction "301_301") (pintype "passive"))
      (node (ref "J3") (pin "304") (pinfunction "304_304") (pintype "passive"))
      (node (ref "J3") (pin "307") (pinfunction "307_307") (pintype "passive"))
      (node (ref "J3") (pin "31") (pinfunction "31_31") (pintype "passive"))
      (node (ref "J3") (pin "310") (pinfunction "310_310") (pintype "passive"))
      (node (ref "J3") (pin "311") (pinfunction "311_311") (pintype "passive"))
      (node (ref "J3") (pin "314") (pinfunction "314_314") (pintype "passive"))
      (node (ref "J3") (pin "317") (pinfunction "317_317") (pintype "passive"))
      (node (ref "J3") (pin "320") (pinfunction "320_320") (pintype "passive"))
      (node (ref "J3") (pin "321") (pinfunction "321_321") (pintype "passive"))
      (node (ref "J3") (pin "324") (pinfunction "324_324") (pintype "passive"))
      (node (ref "J3") (pin "327") (pinfunction "327_327") (pintype "passive"))
      (node (ref "J3") (pin "330") (pinfunction "330_330") (pintype "passive"))
      (node (ref "J3") (pin "331") (pinfunction "331_331") (pintype "passive"))
      (node (ref "J3") (pin "334") (pinfunction "334_334") (pintype "passive"))
      (node (ref "J3") (pin "337") (pinfunction "337_337") (pintype "passive"))
      (node (ref "J3") (pin "34") (pinfunction "34_34") (pintype "passive"))
      (node (ref "J3") (pin "340") (pinfunction "340_340") (pintype "passive"))
      (node (ref "J3") (pin "341") (pinfunction "341_341") (pintype "passive"))
      (node (ref "J3") (pin "344") (pinfunction "344_344") (pintype "passive"))
      (node (ref "J3") (pin "347") (pinfunction "347_347") (pintype "passive"))
      (node (ref "J3") (pin "350") (pinfunction "350_350") (pintype "passive"))
      (node (ref "J3") (pin "351") (pinfunction "351_351") (pintype "passive"))
      (node (ref "J3") (pin "354") (pinfunction "354_354") (pintype "passive"))
      (node (ref "J3") (pin "357") (pinfunction "357_357") (pintype "passive"))
      (node (ref "J3") (pin "360") (pinfunction "360_360") (pintype "passive"))
      (node (ref "J3") (pin "361") (pinfunction "361_361") (pintype "passive"))
      (node (ref "J3") (pin "364") (pinfunction "364_364") (pintype "passive"))
      (node (ref "J3") (pin "367") (pinfunction "367_367") (pintype "passive"))
      (node (ref "J3") (pin "37") (pinfunction "37_37") (pintype "passive"))
      (node (ref "J3") (pin "370") (pinfunction "370_370") (pintype "passive"))
      (node (ref "J3") (pin "371") (pinfunction "371_371") (pintype "passive"))
      (node (ref "J3") (pin "374") (pinfunction "374_374") (pintype "passive"))
      (node (ref "J3") (pin "377") (pinfunction "377_377") (pintype "passive"))
      (node (ref "J3") (pin "380") (pinfunction "380_380") (pintype "passive"))
      (node (ref "J3") (pin "381") (pinfunction "381_381") (pintype "passive"))
      (node (ref "J3") (pin "384") (pinfunction "384_384") (pintype "passive"))
      (node (ref "J3") (pin "387") (pinfunction "387_387") (pintype "passive"))
      (node (ref "J3") (pin "390") (pinfunction "390_390") (pintype "passive"))
      (node (ref "J3") (pin "391") (pinfunction "391_391") (pintype "passive"))
      (node (ref "J3") (pin "394") (pinfunction "394_394") (pintype "passive"))
      (node (ref "J3") (pin "397") (pinfunction "397_397") (pintype "passive"))
      (node (ref "J3") (pin "4") (pinfunction "4_4") (pintype "passive"))
      (node (ref "J3") (pin "40") (pinfunction "40_40") (pintype "passive"))
      (node (ref "J3") (pin "400") (pinfunction "400_400") (pintype "passive"))
      (node (ref "J3") (pin "41") (pinfunction "41_41") (pintype "passive"))
      (node (ref "J3") (pin "44") (pinfunction "44_44") (pintype "passive"))
      (node (ref "J3") (pin "47") (pinfunction "47_47") (pintype "passive"))
      (node (ref "J3") (pin "50") (pinfunction "50_50") (pintype "passive"))
      (node (ref "J3") (pin "51") (pinfunction "51_51") (pintype "passive"))
      (node (ref "J3") (pin "54") (pinfunction "54_54") (pintype "passive"))
      (node (ref "J3") (pin "57") (pinfunction "57_57") (pintype "passive"))
      (node (ref "J3") (pin "60") (pinfunction "60_60") (pintype "passive"))
      (node (ref "J3") (pin "61") (pinfunction "61_61") (pintype "passive"))
      (node (ref "J3") (pin "64") (pinfunction "64_64") (pintype "passive"))
      (node (ref "J3") (pin "67") (pinfunction "67_67") (pintype "passive"))
      (node (ref "J3") (pin "7") (pinfunction "7_7") (pintype "passive"))
      (node (ref "J3") (pin "70") (pinfunction "70_70") (pintype "passive"))
      (node (ref "J3") (pin "71") (pinfunction "71_71") (pintype "passive"))
      (node (ref "J3") (pin "74") (pinfunction "74_74") (pintype "passive"))
      (node (ref "J3") (pin "77") (pinfunction "77_77") (pintype "passive"))
      (node (ref "J3") (pin "80") (pinfunction "80_80") (pintype "passive"))
      (node (ref "J3") (pin "81") (pinfunction "81_81") (pintype "passive"))
      (node (ref "J3") (pin "84") (pinfunction "84_84") (pintype "passive"))
      (node (ref "J3") (pin "87") (pinfunction "87_87") (pintype "passive"))
      (node (ref "J3") (pin "90") (pinfunction "90_90") (pintype "passive"))
      (node (ref "J3") (pin "91") (pinfunction "91_91") (pintype "passive"))
      (node (ref "J3") (pin "94") (pinfunction "94_94") (pintype "passive"))
      (node (ref "J3") (pin "97") (pinfunction "97_97") (pintype "passive"))
    )
    (net (code "188") (name "V1V35") (class "Default")
      (node (ref "R80") (pin "1") (pinfunction "1_1") (pintype "passive"))
      (node (ref "R81") (pin "1") (pinfunction "1_1") (pintype "passive"))
      (node (ref "R82") (pin "1") (pinfunction "1_1") (pintype "passive"))
    )
    (net (code "189") (name "V48") (class "Default")
      (node (ref "J3") (pin "225") (pinfunction "225_225") (pintype "passive"))
      (node (ref "J3") (pin "226") (pinfunction "226_226") (pintype "passive"))
      (node (ref "J3") (pin "228") (pinfunction "228_228") (pintype "passive"))
      (node (ref "J3") (pin "229") (pinfunction "229_229") (pintype "passive"))
      (node (ref "J3") (pin "232") (pinfunction "232_232") (pintype "passive"))
      (node (ref "J3") (pin "233") (pinfunction "233_233") (pintype "passive"))
      (node (ref "J3") (pin "235") (pinfunction "235_235") (pintype "passive"))
      (node (ref "J3") (pin "236") (pinfunction "236_236") (pintype "passive"))
      (node (ref "J3") (pin "238") (pinfunction "238_238") (pintype "passive"))
      (node (ref "J3") (pin "239") (pinfunction "239_239") (pintype "passive"))
      (node (ref "J3") (pin "242") (pinfunction "242_242") (pintype "passive"))
      (node (ref "J3") (pin "243") (pinfunction "243_243") (pintype "passive"))
      (node (ref "J3") (pin "245") (pinfunction "245_245") (pintype "passive"))
      (node (ref "J3") (pin "246") (pinfunction "246_246") (pintype "passive"))
      (node (ref "J3") (pin "248") (pinfunction "248_248") (pintype "passive"))
      (node (ref "J3") (pin "249") (pinfunction "249_249") (pintype "passive"))
    )
    (net (code "190") (name "VTTR") (class "Default")
      (node (ref "R79") (pin "1") (pinfunction "1_1") (pintype "passive"))
    )
    (net (code "191") (name "unconnected-(J3-Pad119)") (class "Default")
      (node (ref "J3") (pin "119") (pinfunction "119_119") (pintype "passive+no_connect"))
    )
    (net (code "192") (name "unconnected-(J3-Pad122)") (class "Default")
      (node (ref "J3") (pin "122") (pinfunction "122_122") (pintype "passive+no_connect"))
    )
    (net (code "193") (name "unconnected-(J3-Pad123)") (class "Default")
      (node (ref "J3") (pin "123") (pinfunction "123_123") (pintype "passive+no_connect"))
    )
    (net (code "194") (name "unconnected-(J3-Pad125)") (class "Default")
      (node (ref "J3") (pin "125") (pinfunction "125_125") (pintype "passive+no_connect"))
    )
    (net (code "195") (name "unconnected-(J3-Pad126)") (class "Default")
      (node (ref "J3") (pin "126") (pinfunction "126_126") (pintype "passive+no_connect"))
    )
    (net (code "196") (name "unconnected-(J3-Pad128)") (class "Default")
      (node (ref "J3") (pin "128") (pinfunction "128_128") (pintype "passive+no_connect"))
    )
    (net (code "197") (name "unconnected-(J3-Pad129)") (class "Default")
      (node (ref "J3") (pin "129") (pinfunction "129_129") (pintype "passive+no_connect"))
    )
    (net (code "198") (name "unconnected-(J3-Pad132)") (class "Default")
      (node (ref "J3") (pin "132") (pinfunction "132_132") (pintype "passive+no_connect"))
    )
    (net (code "199") (name "unconnected-(J3-Pad133)") (class "Default")
      (node (ref "J3") (pin "133") (pinfunction "133_133") (pintype "passive+no_connect"))
    )
    (net (code "200") (name "unconnected-(J3-Pad135)") (class "Default")
      (node (ref "J3") (pin "135") (pinfunction "135_135") (pintype "passive+no_connect"))
    )
    (net (code "201") (name "unconnected-(J3-Pad136)") (class "Default")
      (node (ref "J3") (pin "136") (pinfunction "136_136") (pintype "passive+no_connect"))
    )
    (net (code "202") (name "unconnected-(J3-Pad138)") (class "Default")
      (node (ref "J3") (pin "138") (pinfunction "138_138") (pintype "passive+no_connect"))
    )
    (net (code "203") (name "unconnected-(J3-Pad139)") (class "Default")
      (node (ref "J3") (pin "139") (pinfunction "139_139") (pintype "passive+no_connect"))
    )
    (net (code "204") (name "unconnected-(J3-Pad142)") (class "Default")
      (node (ref "J3") (pin "142") (pinfunction "142_142") (pintype "passive+no_connect"))
    )
    (net (code "205") (name "unconnected-(J3-Pad143)") (class "Default")
      (node (ref "J3") (pin "143") (pinfunction "143_143") (pintype "passive+no_connect"))
    )
    (net (code "206") (name "unconnected-(J3-Pad145)") (class "Default")
      (node (ref "J3") (pin "145") (pinfunction "145_145") (pintype "passive+no_connect"))
    )
    (net (code "207") (name "unconnected-(J3-Pad146)") (class "Default")
      (node (ref "J3") (pin "146") (pinfunction "146_146") (pintype "passive+no_connect"))
    )
    (net (code "208") (name "unconnected-(J3-Pad148)") (class "Default")
      (node (ref "J3") (pin "148") (pinfunction "148_148") (pintype "passive+no_connect"))
    )
    (net (code "209") (name "unconnected-(J3-Pad149)") (class "Default")
      (node (ref "J3") (pin "149") (pinfunction "149_149") (pintype "passive+no_connect"))
    )
    (net (code "210") (name "unconnected-(J3-Pad212)") (class "Default")
      (node (ref "J3") (pin "212") (pinfunction "212_212") (pintype "passive"))
    )
    (net (code "211") (name "unconnected-(J3-Pad213)") (class "Default")
      (node (ref "J3") (pin "213") (pinfunction "213_213") (pintype "passive"))
    )
    (net (code "212") (name "unconnected-(J3-Pad215)") (class "Default")
      (node (ref "J3") (pin "215") (pinfunction "215_215") (pintype "passive"))
    )
    (net (code "213") (name "unconnected-(J3-Pad216)") (class "Default")
      (node (ref "J3") (pin "216") (pinfunction "216_216") (pintype "passive"))
    )
    (net (code "214") (name "unconnected-(J3-Pad319)") (class "Default")
      (node (ref "J3") (pin "319") (pinfunction "319_319") (pintype "passive+no_connect"))
    )
  )
)
